# PCB_V1.net
KiCad netlist of a schematic drawn in EAGLE
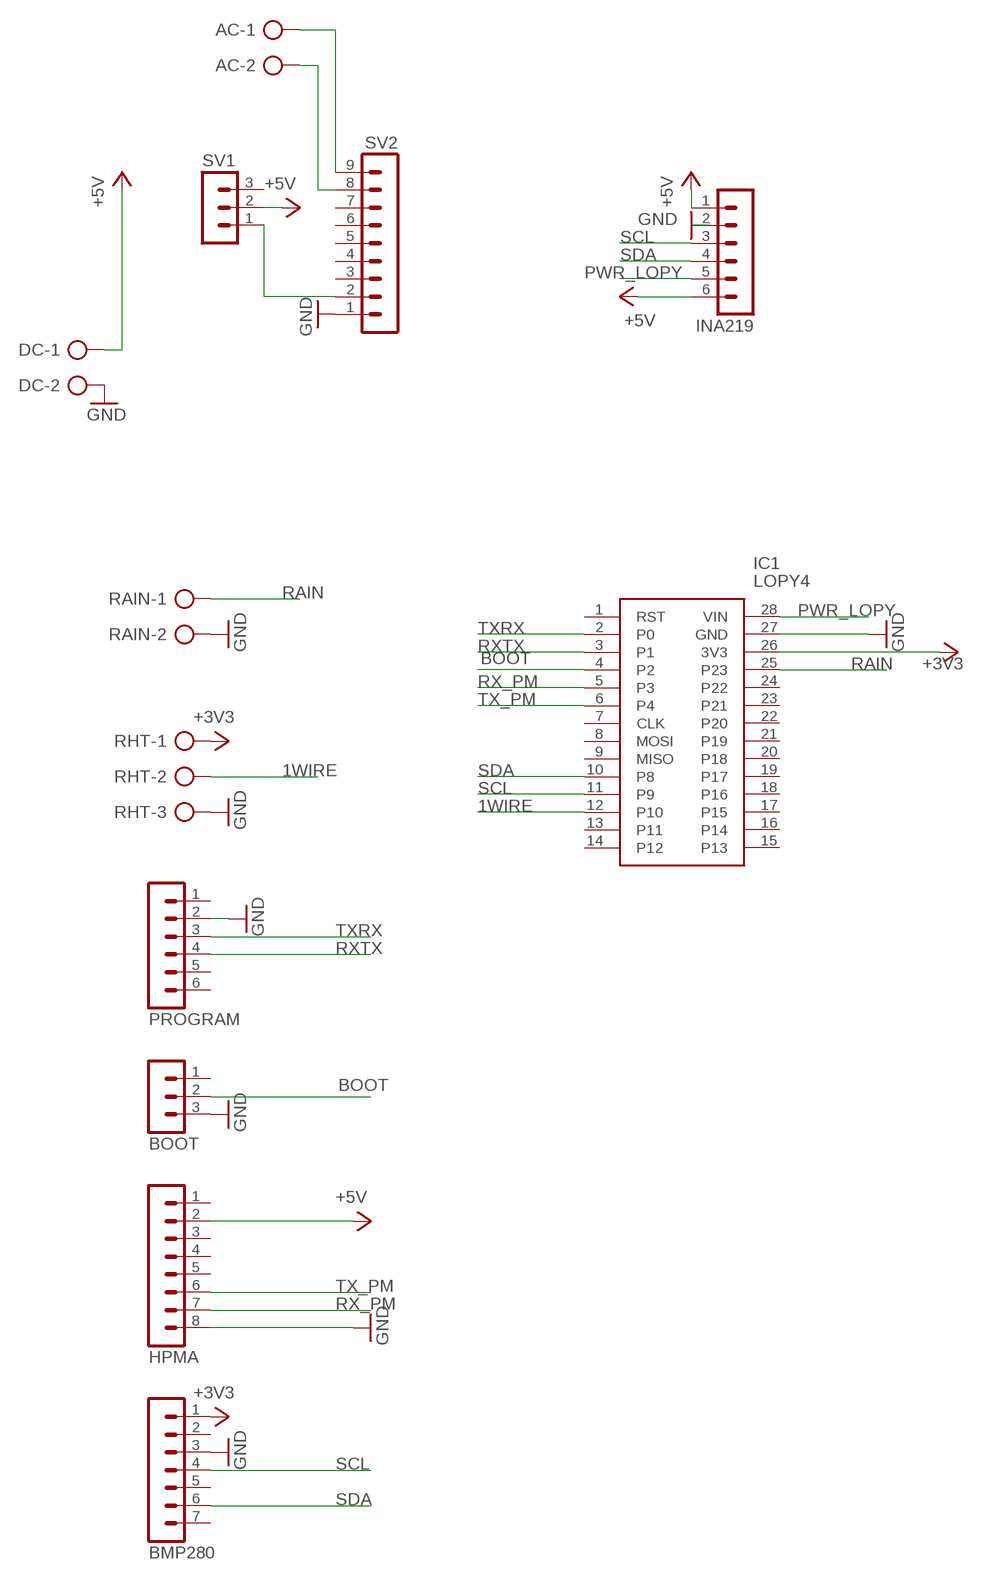
[diagram p0: schematic, sheet 1]

(export (version "E")
  (design (tool "Eeschema 10.0.6"))
  (components
    (comp (ref "AC")
      (value "AK300/2")
      (footprint "eagle-import:AK300_2")
      (libsource (lib "eagle-import") (part "AK300/2"))
    )
    (comp (ref "BMP280")
      (value "MA07-1")
      (footprint "eagle-import:MA07-1")
      (libsource (lib "eagle-import") (part "MA07-1"))
    )
    (comp (ref "BOOT")
      (value "MA03-1")
      (footprint "eagle-import:MA03-1")
      (libsource (lib "eagle-import") (part "MA03-1"))
    )
    (comp (ref "DC")
      (value "AK300/2")
      (footprint "eagle-import:AK300_2")
      (libsource (lib "eagle-import") (part "AK300/2"))
    )
    (comp (ref "HPMA")
      (value "MA08-1")
      (footprint "eagle-import:MA08-1")
      (libsource (lib "eagle-import") (part "MA08-1"))
    )
    (comp (ref "IC1")
      (value "LOPY4")
      (footprint "eagle-import:LOPY4")
      (fields (field (name "MOUSER_PART_NUMBER") "365-LOPY4"))
      (libsource (lib "eagle-import") (part "LOPY4"))
    )
    (comp (ref "INA219")
      (value "MA06-1")
      (footprint "eagle-import:MA06-1")
      (libsource (lib "eagle-import") (part "MA06-1"))
    )
    (comp (ref "PROGRAM")
      (value "MA06-1")
      (footprint "eagle-import:MA06-1")
      (libsource (lib "eagle-import") (part "MA06-1"))
    )
    (comp (ref "RAIN")
      (value "AK300/2")
      (footprint "eagle-import:AK300_2")
      (libsource (lib "eagle-import") (part "AK300/2"))
    )
    (comp (ref "RHT")
      (value "AK300/3")
      (footprint "eagle-import:AK300_3")
      (libsource (lib "eagle-import") (part "AK300/3"))
    )
    (comp (ref "SV1")
      (value "MA03-1")
      (footprint "eagle-import:MA03-1")
      (libsource (lib "eagle-import") (part "MA03-1"))
    )
    (comp (ref "SV2")
      (value "MA09-1")
      (footprint "eagle-import:MA09-1")
      (libsource (lib "eagle-import") (part "MA09-1"))
    )
  )
  (nets
    (net (code "1") (name "+3V3") (class "Default")
      (node (ref "BMP280") (pin "1") (pinfunction "1_1") (pintype "passive"))
      (node (ref "IC1") (pin "26") (pinfunction "3V3_26") (pintype "bidirectional"))
      (node (ref "RHT") (pin "1") (pinfunction "KL_1") (pintype "passive"))
    )
    (net (code "2") (name "+5V") (class "Default")
      (node (ref "DC") (pin "1") (pinfunction "KL_1") (pintype "passive"))
      (node (ref "HPMA") (pin "2") (pinfunction "2_2") (pintype "passive"))
      (node (ref "INA219") (pin "1") (pinfunction "1_1") (pintype "passive"))
      (node (ref "INA219") (pin "6") (pinfunction "6_6") (pintype "passive"))
      (node (ref "SV1") (pin "2") (pinfunction "2_2") (pintype "passive"))
    )
    (net (code "3") (name "/1WIRE") (class "Default")
      (node (ref "IC1") (pin "12") (pinfunction "P10_12") (pintype "bidirectional"))
      (node (ref "RHT") (pin "2") (pinfunction "KL_2") (pintype "passive"))
    )
    (net (code "4") (name "/BOOT") (class "Default")
      (node (ref "BOOT") (pin "2") (pinfunction "2_2") (pintype "passive"))
      (node (ref "IC1") (pin "4") (pinfunction "P2_4") (pintype "bidirectional"))
    )
    (net (code "5") (name "/PWR_LOPY") (class "Default")
      (node (ref "IC1") (pin "28") (pinfunction "VIN_28") (pintype "bidirectional"))
      (node (ref "INA219") (pin "5") (pinfunction "5_5") (pintype "passive"))
    )
    (net (code "6") (name "/RAIN") (class "Default")
      (node (ref "IC1") (pin "25") (pinfunction "P23_25") (pintype "bidirectional"))
      (node (ref "RAIN") (pin "1") (pinfunction "KL_1") (pintype "passive"))
    )
    (net (code "7") (name "/RXTX") (class "Default")
      (node (ref "IC1") (pin "3") (pinfunction "P1_3") (pintype "bidirectional"))
      (node (ref "PROGRAM") (pin "4") (pinfunction "4_4") (pintype "passive"))
    )
    (net (code "8") (name "/RX_PM") (class "Default")
      (node (ref "HPMA") (pin "7") (pinfunction "7_7") (pintype "passive"))
      (node (ref "IC1") (pin "5") (pinfunction "P3_5") (pintype "bidirectional"))
    )
    (net (code "9") (name "/SCL") (class "Default")
      (node (ref "BMP280") (pin "4") (pinfunction "4_4") (pintype "passive"))
      (node (ref "IC1") (pin "11") (pinfunction "P9_11") (pintype "bidirectional"))
      (node (ref "INA219") (pin "3") (pinfunction "3_3") (pintype "passive"))
    )
    (net (code "10") (name "/SDA") (class "Default")
      (node (ref "BMP280") (pin "6") (pinfunction "6_6") (pintype "passive"))
      (node (ref "IC1") (pin "10") (pinfunction "P8_10") (pintype "bidirectional"))
      (node (ref "INA219") (pin "4") (pinfunction "4_4") (pintype "passive"))
    )
    (net (code "11") (name "/TXRX") (class "Default")
      (node (ref "IC1") (pin "2") (pinfunction "P0_2") (pintype "bidirectional"))
      (node (ref "PROGRAM") (pin "3") (pinfunction "3_3") (pintype "passive"))
    )
    (net (code "12") (name "/TX_PM") (class "Default")
      (node (ref "HPMA") (pin "6") (pinfunction "6_6") (pintype "passive"))
      (node (ref "IC1") (pin "6") (pinfunction "P4_6") (pintype "bidirectional"))
    )
    (net (code "13") (name "GND") (class "Default")
      (node (ref "BMP280") (pin "3") (pinfunction "3_3") (pintype "passive"))
      (node (ref "BOOT") (pin "3") (pinfunction "3_3") (pintype "passive"))
      (node (ref "DC") (pin "2") (pinfunction "KL_2") (pintype "passive"))
      (node (ref "HPMA") (pin "8") (pinfunction "8_8") (pintype "passive"))
      (node (ref "IC1") (pin "27") (pinfunction "GND_27") (pintype "bidirectional"))
      (node (ref "INA219") (pin "2") (pinfunction "2_2") (pintype "passive"))
      (node (ref "PROGRAM") (pin "2") (pinfunction "2_2") (pintype "passive"))
      (node (ref "RAIN") (pin "2") (pinfunction "KL_2") (pintype "passive"))
      (node (ref "RHT") (pin "3") (pinfunction "KL_3") (pintype "passive"))
      (node (ref "SV2") (pin "1") (pinfunction "1_1") (pintype "passive"))
    )
    (net (code "14") (name "Net-(ACA-KL)") (class "Default")
      (node (ref "AC") (pin "1") (pinfunction "KL_1") (pintype "passive"))
      (node (ref "SV2") (pin "9") (pinfunction "9_9") (pintype "passive"))
    )
    (net (code "15") (name "Net-(ACB-KL)") (class "Default")
      (node (ref "AC") (pin "2") (pinfunction "KL_2") (pintype "passive"))
      (node (ref "SV2") (pin "8") (pinfunction "8_8") (pintype "passive"))
    )
    (net (code "16") (name "Net-(SV1-Pad1)") (class "Default")
      (node (ref "SV1") (pin "1") (pinfunction "1_1") (pintype "passive"))
      (node (ref "SV2") (pin "2") (pinfunction "2_2") (pintype "passive"))
    )
    (net (code "17") (name "unconnected-(BMP280-Pad2)") (class "Default")
      (node (ref "BMP280") (pin "2") (pinfunction "2_2") (pintype "passive"))
    )
    (net (code "18") (name "unconnected-(BMP280-Pad5)") (class "Default")
      (node (ref "BMP280") (pin "5") (pinfunction "5_5") (pintype "passive"))
    )
    (net (code "19") (name "unconnected-(BMP280-Pad7)") (class "Default")
      (node (ref "BMP280") (pin "7") (pinfunction "7_7") (pintype "passive"))
    )
    (net (code "20") (name "unconnected-(BOOT-Pad1)") (class "Default")
      (node (ref "BOOT") (pin "1") (pinfunction "1_1") (pintype "passive"))
    )
    (net (code "21") (name "unconnected-(HPMA-Pad1)") (class "Default")
      (node (ref "HPMA") (pin "1") (pinfunction "1_1") (pintype "passive"))
    )
    (net (code "22") (name "unconnected-(HPMA-Pad3)") (class "Default")
      (node (ref "HPMA") (pin "3") (pinfunction "3_3") (pintype "passive"))
    )
    (net (code "23") (name "unconnected-(HPMA-Pad4)") (class "Default")
      (node (ref "HPMA") (pin "4") (pinfunction "4_4") (pintype "passive"))
    )
    (net (code "24") (name "unconnected-(HPMA-Pad5)") (class "Default")
      (node (ref "HPMA") (pin "5") (pinfunction "5_5") (pintype "passive"))
    )
    (net (code "25") (name "unconnected-(IC1-CLK-Pad7)") (class "Default")
      (node (ref "IC1") (pin "7") (pinfunction "CLK_7") (pintype "bidirectional"))
    )
    (net (code "26") (name "unconnected-(IC1-MISO-Pad9)") (class "Default")
      (node (ref "IC1") (pin "9") (pinfunction "MISO_9") (pintype "bidirectional"))
    )
    (net (code "27") (name "unconnected-(IC1-MOSI-Pad8)") (class "Default")
      (node (ref "IC1") (pin "8") (pinfunction "MOSI_8") (pintype "bidirectional"))
    )
    (net (code "28") (name "unconnected-(IC1-P11-Pad13)") (class "Default")
      (node (ref "IC1") (pin "13") (pinfunction "P11_13") (pintype "bidirectional"))
    )
    (net (code "29") (name "unconnected-(IC1-P12-Pad14)") (class "Default")
      (node (ref "IC1") (pin "14") (pinfunction "P12_14") (pintype "bidirectional"))
    )
    (net (code "30") (name "unconnected-(IC1-P13-Pad15)") (class "Default")
      (node (ref "IC1") (pin "15") (pinfunction "P13_15") (pintype "bidirectional"))
    )
    (net (code "31") (name "unconnected-(IC1-P14-Pad16)") (class "Default")
      (node (ref "IC1") (pin "16") (pinfunction "P14_16") (pintype "bidirectional"))
    )
    (net (code "32") (name "unconnected-(IC1-P15-Pad17)") (class "Default")
      (node (ref "IC1") (pin "17") (pinfunction "P15_17") (pintype "bidirectional"))
    )
    (net (code "33") (name "unconnected-(IC1-P16-Pad18)") (class "Default")
      (node (ref "IC1") (pin "18") (pinfunction "P16_18") (pintype "bidirectional"))
    )
    (net (code "34") (name "unconnected-(IC1-P17-Pad19)") (class "Default")
      (node (ref "IC1") (pin "19") (pinfunction "P17_19") (pintype "bidirectional"))
    )
    (net (code "35") (name "unconnected-(IC1-P18-Pad20)") (class "Default")
      (node (ref "IC1") (pin "20") (pinfunction "P18_20") (pintype "bidirectional"))
    )
    (net (code "36") (name "unconnected-(IC1-P19-Pad21)") (class "Default")
      (node (ref "IC1") (pin "21") (pinfunction "P19_21") (pintype "bidirectional"))
    )
    (net (code "37") (name "unconnected-(IC1-P20-Pad22)") (class "Default")
      (node (ref "IC1") (pin "22") (pinfunction "P20_22") (pintype "bidirectional"))
    )
    (net (code "38") (name "unconnected-(IC1-P21-Pad23)") (class "Default")
      (node (ref "IC1") (pin "23") (pinfunction "P21_23") (pintype "bidirectional"))
    )
    (net (code "39") (name "unconnected-(IC1-P22-Pad24)") (class "Default")
      (node (ref "IC1") (pin "24") (pinfunction "P22_24") (pintype "bidirectional"))
    )
    (net (code "40") (name "unconnected-(IC1-RST-Pad1)") (class "Default")
      (node (ref "IC1") (pin "1") (pinfunction "RST_1") (pintype "bidirectional"))
    )
    (net (code "41") (name "unconnected-(PROGRAM-Pad1)") (class "Default")
      (node (ref "PROGRAM") (pin "1") (pinfunction "1_1") (pintype "passive"))
    )
    (net (code "42") (name "unconnected-(PROGRAM-Pad5)") (class "Default")
      (node (ref "PROGRAM") (pin "5") (pinfunction "5_5") (pintype "passive"))
    )
    (net (code "43") (name "unconnected-(PROGRAM-Pad6)") (class "Default")
      (node (ref "PROGRAM") (pin "6") (pinfunction "6_6") (pintype "passive"))
    )
    (net (code "44") (name "unconnected-(SV1-Pad3)") (class "Default")
      (node (ref "SV1") (pin "3") (pinfunction "3_3") (pintype "passive"))
    )
    (net (code "45") (name "unconnected-(SV2-Pad3)") (class "Default")
      (node (ref "SV2") (pin "3") (pinfunction "3_3") (pintype "passive"))
    )
    (net (code "46") (name "unconnected-(SV2-Pad4)") (class "Default")
      (node (ref "SV2") (pin "4") (pinfunction "4_4") (pintype "passive"))
    )
    (net (code "47") (name "unconnected-(SV2-Pad5)") (class "Default")
      (node (ref "SV2") (pin "5") (pinfunction "5_5") (pintype "passive"))
    )
    (net (code "48") (name "unconnected-(SV2-Pad6)") (class "Default")
      (node (ref "SV2") (pin "6") (pinfunction "6_6") (pintype "passive"))
    )
    (net (code "49") (name "unconnected-(SV2-Pad7)") (class "Default")
      (node (ref "SV2") (pin "7") (pinfunction "7_7") (pintype "passive"))
    )
  )
)
